# Flash.net
KiCad netlist of a schematic drawn in Altium Designer
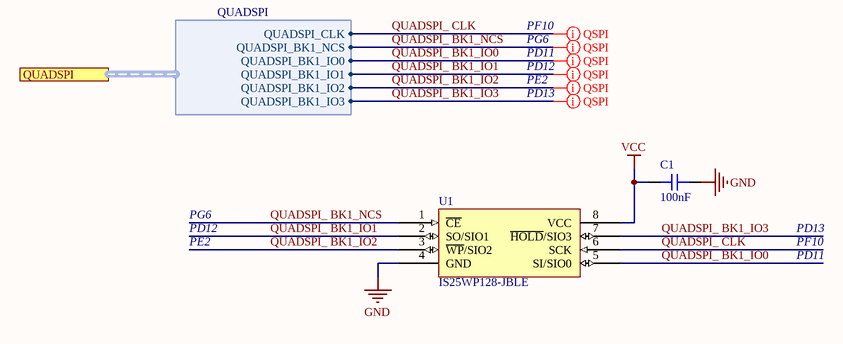
[diagram p0: Flash.SchDoc]

(export (version "E")
  (design (tool "Eeschema 10.0.6"))
  (components
    (comp (ref "C1")
      (value "100nF")
      (footprint "Capacitor-0603")
      (fields (field (name "Comment") "C-100nF-0603"))
      (libsource (lib "Components") (part "C-100nF-0603"))
    )
    (comp (ref "U1")
      (value "IS25WP128-JBLE")
      (footprint "IS25WP128-JBLE")
      (libsource (lib "Components") (part "IS25WP128-JBLE"))
    )
  )
  (nets
    (net (code "2") (name "/QUADSPI_ BK1_IO0") (class "Default")
      (node (ref "U1") (pin "5") (pinfunction "SI/SIO0_5") (pintype "bidirectional"))
    )
    (net (code "3") (name "/QUADSPI_ BK1_IO1") (class "Default")
      (node (ref "U1") (pin "2") (pinfunction "SO/SIO1_2") (pintype "bidirectional"))
    )
    (net (code "4") (name "/QUADSPI_ BK1_IO2") (class "Default")
      (node (ref "U1") (pin "3") (pinfunction "~{WP}/SIO2_3") (pintype "bidirectional"))
    )
    (net (code "5") (name "/QUADSPI_ BK1_IO3") (class "Default")
      (node (ref "U1") (pin "7") (pinfunction "~{HOLD}/SIO3_7") (pintype "bidirectional"))
    )
    (net (code "6") (name "/QUADSPI_ BK1_NCS") (class "Default")
      (node (ref "U1") (pin "1") (pinfunction "~{CE}_1") (pintype "input"))
    )
    (net (code "7") (name "/QUADSPI_ CLK") (class "Default")
      (node (ref "U1") (pin "6") (pinfunction "SCK_6") (pintype "input"))
    )
    (net (code "9") (name "GND") (class "Default")
      (node (ref "C1") (pin "2") (pinfunction "2_2") (pintype "passive"))
      (node (ref "U1") (pin "4") (pinfunction "GND_4") (pintype "power_in"))
    )
    (net (code "10") (name "VCC") (class "Default")
      (node (ref "C1") (pin "1") (pinfunction "1_1") (pintype "passive"))
      (node (ref "U1") (pin "8") (pinfunction "VCC_8") (pintype "power_in"))
    )
  )
)
